# PowerV3.net
KiCad netlist of a schematic drawn in Altium Designer
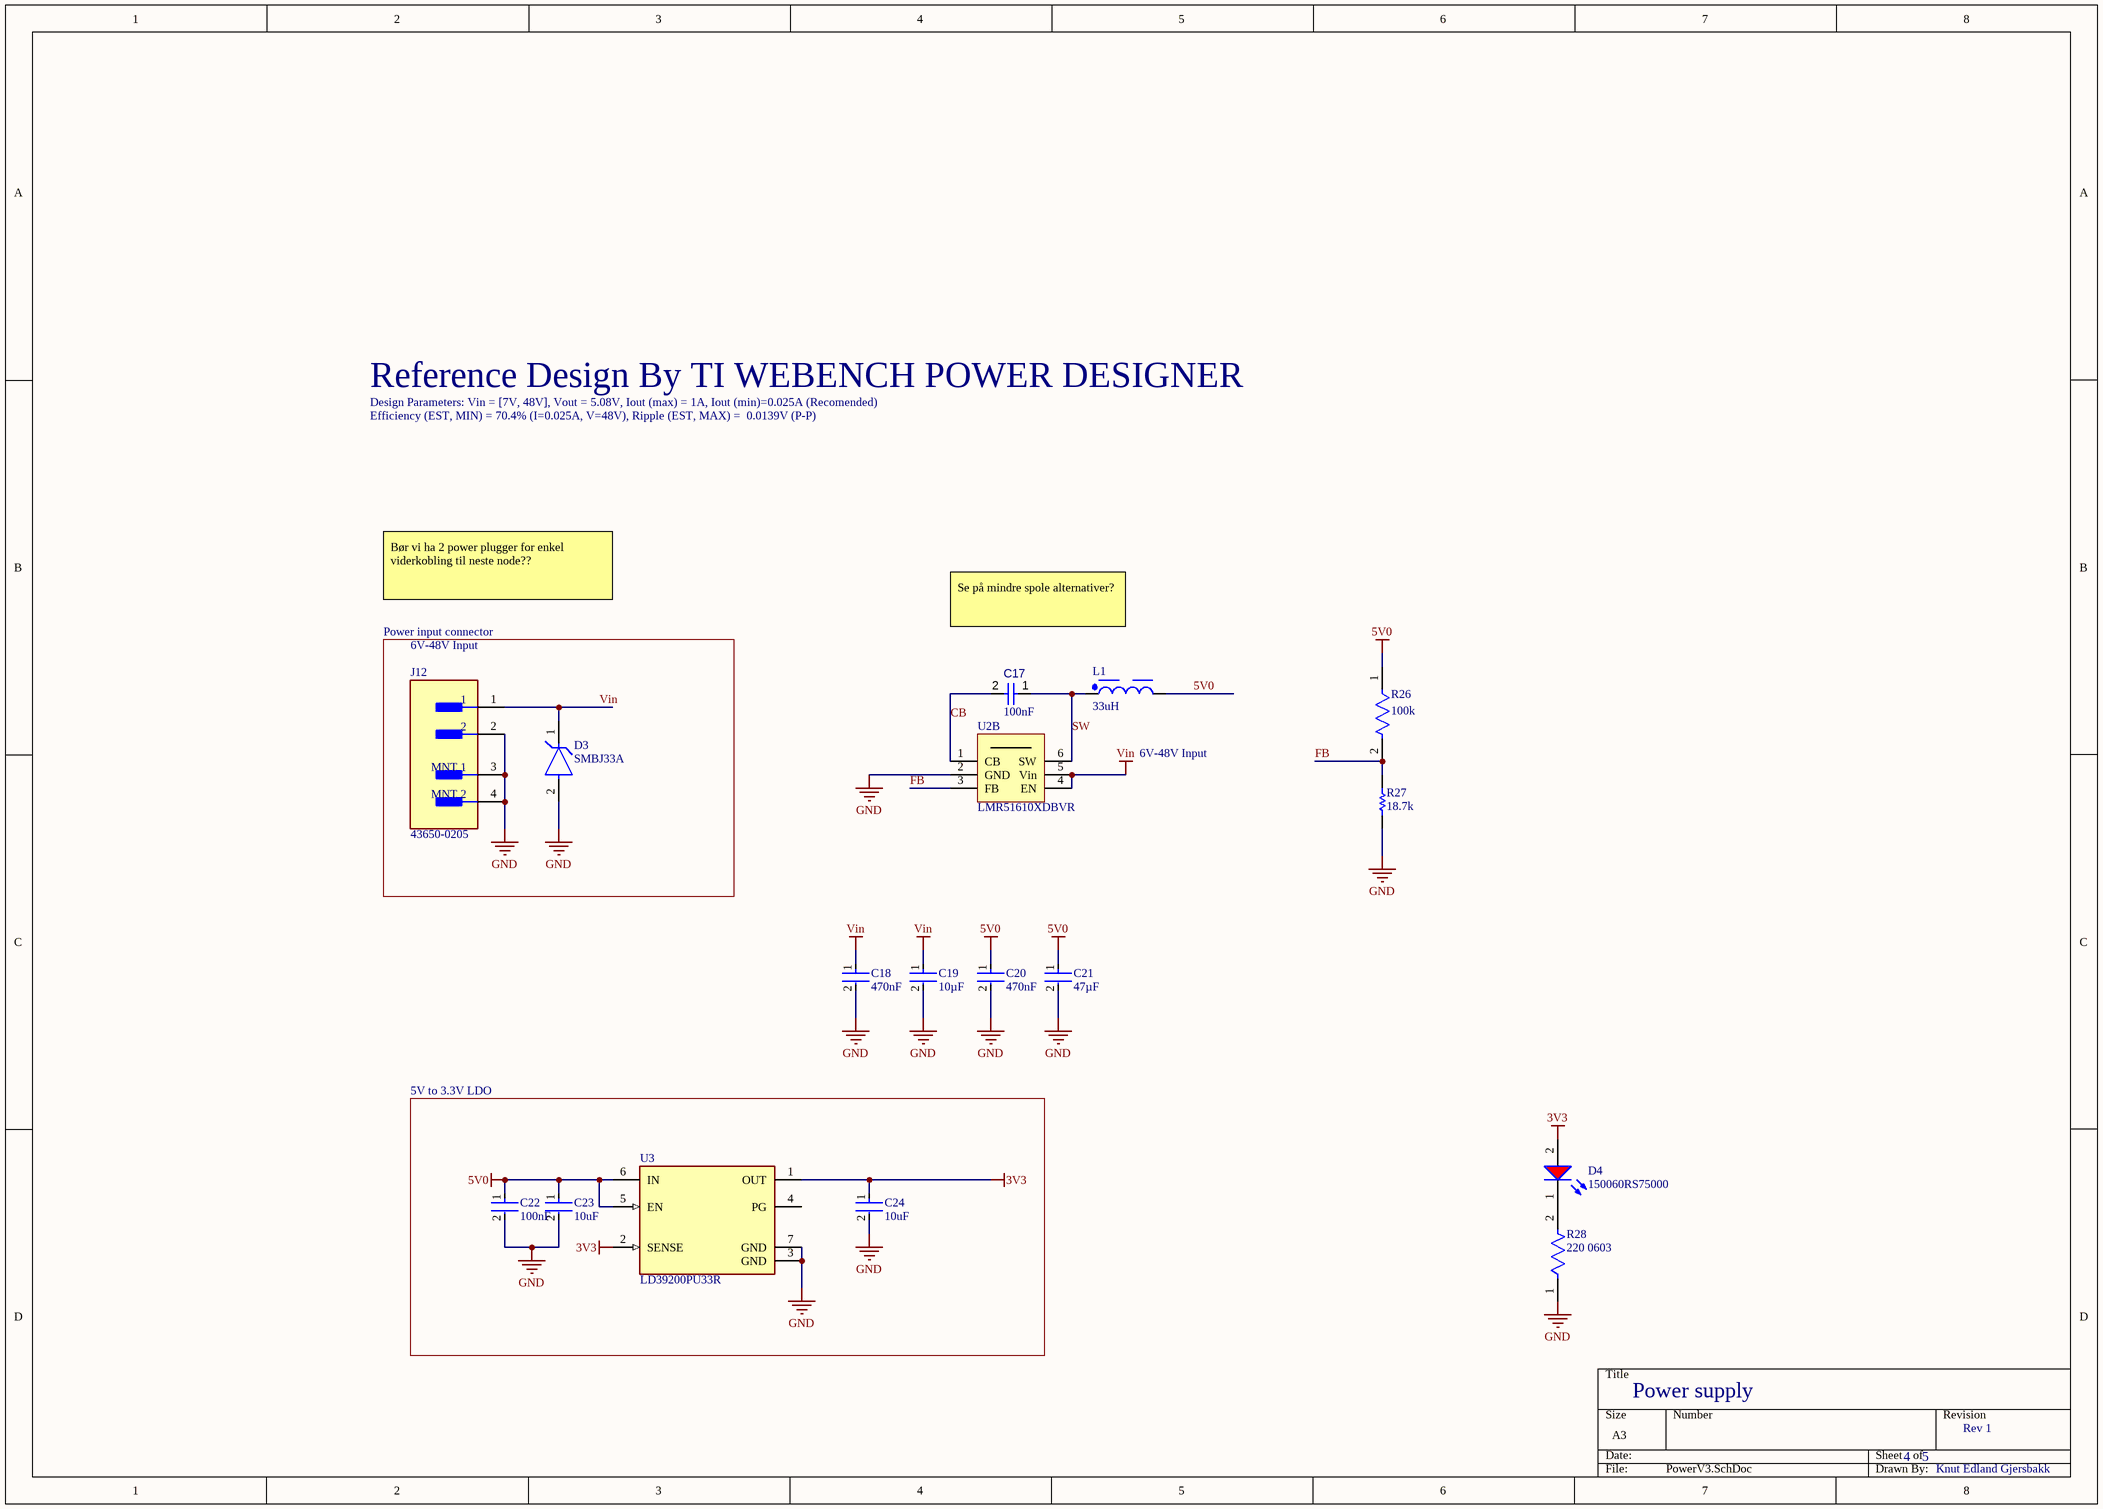
[diagram p0: PowerV3.SchDoc]

(export (version "E")
  (design (tool "Eeschema 10.0.6"))
  (components
    (comp (ref "C17")
      (value "100nF")
      (footprint "CAPC2013X95X50LL10T25")
      (description "Chip Capacitor, 100 nF, +/- 10%, 50 V, 0805 (2012 Metric)")
      (fields (field (name "TOLERANCE") "10%") (field (name "Comment") "Capacitor 100 nF +/-10% 50 V 0805"))
      (libsource (lib "UiS Aerospace") (part "CAP-NP-2"))
    )
    (comp (ref "C18")
      (value "470nF")
      (footprint "FP-CL21-IPC_A")
      (fields (field (name "Comment") "CL21B474KBFNNNF"))
      (libsource (lib "UiS Aerospace") (part "b4654b650e69147ec39a6b967a45e02"))
    )
    (comp (ref "C19")
      (value "10µF")
      (footprint "FP-CL31B106KBHNNNE-IPC_A")
      (fields (field (name "Comment") "CL31B106KBHNNNE"))
      (libsource (lib "UiS Aerospace") (part "b4654b650e69147ec39a6b967a45e02"))
    )
    (comp (ref "C20")
      (value "470nF")
      (footprint "FP-CL21-IPC_A")
      (fields (field (name "Comment") "CL21B474KBFNNNF"))
      (libsource (lib "UiS Aerospace") (part "b4654b650e69147ec39a6b967a45e02"))
    )
    (comp (ref "C21")
      (value "47µF")
      (footprint "FP-GRM31C-0_2-e0_3_0_8-IPC_B")
      (fields (field (name "Comment") "GRM31CR61A476KE15K"))
      (libsource (lib "UiS Aerospace") (part "02cd4be3c70576c341d710602a673aa"))
    )
    (comp (ref "C22")
      (value "100nF")
      (footprint "FP-CL10-IPC_C")
      (description "Cap Ceramic 100nF 16V X7R ±10% Pad SMD 0603 +125°C T/R\r\nCL10B104KO8WPNC")
      (fields (field (name "TOLERANCE") "10%"))
      (libsource (lib "Altium Content Vault") (part "b4654b650e69147ec39a6b967a45e02"))
    )
    (comp (ref "C23")
      (value "10uF")
      (footprint "FP-CL10-IPC_C")
      (description "Cap Ceramic 10uF 16V X6S ±20% Pad SMD 0603 +105°C T/R\r\nCL10X106MO8NRNC")
      (fields (field (name "TOLERANCE") "20%"))
      (libsource (lib "Altium Content Vault") (part "b4654b650e69147ec39a6b967a45e02"))
    )
    (comp (ref "C24")
      (value "10uF")
      (footprint "FP-CL10-IPC_C")
      (description "Cap Ceramic 10uF 16V X6S ±20% Pad SMD 0603 +105°C T/R\r\nCL10X106MO8NRNC")
      (fields (field (name "TOLERANCE") "20%"))
      (libsource (lib "Altium Content Vault") (part "b4654b650e69147ec39a6b967a45e02"))
    )
    (comp (ref "D3")
      (value "SMBJ33A")
      (footprint "FP-SMBJ-MFG")
      (description "TVS DIODE 33V 53.3V DO214AA")
      (fields
        (field (name "MANUFACTURER") "Littelfuse Inc")
        (field (name "OCTOPART") "https://octopart.com/smbj33a-littelfuse-350829")
      )
      (libsource (lib "Altium Content Vault") (part "f813f71cba58e380607f5dd3caf9714"))
    )
    (comp (ref "D4")
      (value "150060RS75000")
      (footprint "WL-SMCW_0603_150060xx75000")
      (description "LED Low-Power Uni-Color Red 630nm 2V 2-Pin Chip 0603(1608Metric) T/R")
      (libsource (lib "Altium Content Vault") (part "LED_Red_2A-1K"))
    )
    (comp (ref "J12")
      (value "43650-0205")
      (footprint "FP-43650-0205-MFG")
      (description "43650-0205 Conn Wire to Board HDR 2 POS 3mm Solder RA Side Entry Thru-Hole Micro-Fit 3.0™ Tray")
      (libsource (lib "Altium Content Vault") (part "56ec3178a87b3978bdc1b3682cd516a"))
    )
    (comp (ref "L1")
      (value "33uH")
      (footprint "WE-PD_1260P")
      (description "General Purpose Inductor")
      (fields (field (name "Comment") "7447706330"))
      (libsource (lib "UiS Aerospace") (part "Inductor - 2"))
    )
    (comp (ref "R26")
      (value "100k")
      (footprint "FP-CRGCQ1206-IPC_A")
      (fields (field (name "Comment") "CRGCQ1206F100K"))
      (libsource (lib "UiS Aerospace") (part "1029c3af85768c4190bb7ad29bc67b5"))
    )
    (comp (ref "R27")
      (value "18.7k")
      (footprint "RESC2013X60X40LL20T25")
      (description "Fixed Resistor, Thin Film, 0.125W, 18700ohm, 100V, 0.1% +/-Tol, 25ppm/Cel, Surface Mount, 0805")
      (fields (field (name "TOLERANCE") "0.1%") (field (name "POWER") "125mW"))
      (libsource (lib "UiS Aerospace") (part "RES"))
    )
    (comp (ref "R28")
      (value "220 0603")
      (footprint "FP-AF0603-IPC_C")
      (description "AF0603JR-07220RL Anti-Sulfurated Chip Resistors Automotive Grade 220Ω 5% 100ppm/°C 0603")
      (fields (field (name "TOLERANCE") "5%"))
      (libsource (lib "Altium Content Vault") (part "1029c3af85768c4190bb7ad29bc67b5"))
    )
    (comp (ref "U2")
      (value "LMR51610XDBVR")
      (footprint "SOT95P280X145-6N")
      (description "SIMPLE SWITCHER® 4.5-V to 65-V, 1-A synchronous buck converter with 25-µA IQ 6-SOT-23 -40 to 150")
      (libsource (lib "UiS Aerospace") (part "LMR51610XDBVR-Symbol-1"))
    )
    (comp (ref "U3")
      (value "LD39200PU33R")
      (footprint "FP-DFN6-7946637-MFG")
      (description "IC REG LINEAR 3.3V 2A 6DFN")
      (libsource (lib "Altium Content Vault") (part "f0cfe00d12cb984572f50007c934a2d"))
    )
  )
  (nets
    (net (code "1") (name "/CB") (class "Default")
      (node (ref "C17") (pin "2") (pinfunction "2_2") (pintype "passive"))
      (node (ref "U2") (pin "1") (pinfunction "CB_1") (pintype "passive"))
    )
    (net (code "2") (name "/FB") (class "Default")
      (node (ref "R26") (pin "2") (pinfunction "2_2") (pintype "passive"))
      (node (ref "R27") (pin "1") (pinfunction "1_1") (pintype "passive"))
      (node (ref "U2") (pin "3") (pinfunction "FB_3") (pintype "passive"))
    )
    (net (code "3") (name "/SW") (class "Default")
      (node (ref "C17") (pin "1") (pinfunction "1_1") (pintype "passive"))
      (node (ref "L1") (pin "1") (pinfunction "1_1") (pintype "passive"))
      (node (ref "U2") (pin "6") (pinfunction "SW_6") (pintype "passive"))
    )
    (net (code "4") (name "3V3") (class "Default")
      (node (ref "C24") (pin "1") (pinfunction "1_1") (pintype "passive"))
      (node (ref "D4") (pin "2") (pinfunction "A_2") (pintype "passive"))
      (node (ref "U3") (pin "1") (pinfunction "OUT_1") (pintype "power_in"))
      (node (ref "U3") (pin "2") (pinfunction "SENSE_2") (pintype "input"))
    )
    (net (code "5") (name "5V0") (class "Default")
      (node (ref "C20") (pin "1") (pinfunction "1_1") (pintype "passive"))
      (node (ref "C21") (pin "1") (pinfunction "1_1") (pintype "passive"))
      (node (ref "C22") (pin "1") (pinfunction "1_1") (pintype "passive"))
      (node (ref "C23") (pin "1") (pinfunction "1_1") (pintype "passive"))
      (node (ref "L1") (pin "2") (pinfunction "2_2") (pintype "passive"))
      (node (ref "R26") (pin "1") (pinfunction "1_1") (pintype "passive"))
      (node (ref "U3") (pin "5") (pinfunction "EN_5") (pintype "input"))
      (node (ref "U3") (pin "6") (pinfunction "IN_6") (pintype "power_in"))
    )
    (net (code "6") (name "GND") (class "Default")
      (node (ref "C18") (pin "2") (pinfunction "2_2") (pintype "passive"))
      (node (ref "C19") (pin "2") (pinfunction "2_2") (pintype "passive"))
      (node (ref "C20") (pin "2") (pinfunction "2_2") (pintype "passive"))
      (node (ref "C21") (pin "2") (pinfunction "2_2") (pintype "passive"))
      (node (ref "C22") (pin "2") (pinfunction "2_2") (pintype "passive"))
      (node (ref "C23") (pin "2") (pinfunction "2_2") (pintype "passive"))
      (node (ref "C24") (pin "2") (pinfunction "2_2") (pintype "passive"))
      (node (ref "D3") (pin "2") (pinfunction "A_2") (pintype "passive"))
      (node (ref "J12") (pin "2") (pinfunction "2_2") (pintype "passive"))
      (node (ref "J12") (pin "3") (pinfunction "MNT_1_3") (pintype "passive"))
      (node (ref "J12") (pin "4") (pinfunction "MNT_2_4") (pintype "passive"))
      (node (ref "R27") (pin "2") (pinfunction "2_2") (pintype "passive"))
      (node (ref "R28") (pin "1") (pinfunction "1_1") (pintype "passive"))
      (node (ref "U2") (pin "2") (pinfunction "GND_2") (pintype "passive"))
      (node (ref "U3") (pin "3") (pinfunction "GND_3") (pintype "power_in"))
      (node (ref "U3") (pin "7") (pinfunction "GND_7") (pintype "power_in"))
    )
    (net (code "7") (name "Net-(D4-K)") (class "Default")
      (node (ref "D4") (pin "1") (pinfunction "K_1") (pintype "passive"))
      (node (ref "R28") (pin "2") (pinfunction "2_2") (pintype "passive"))
    )
    (net (code "8") (name "Vin") (class "Default")
      (node (ref "C18") (pin "1") (pinfunction "1_1") (pintype "passive"))
      (node (ref "C19") (pin "1") (pinfunction "1_1") (pintype "passive"))
      (node (ref "D3") (pin "1") (pinfunction "C_1") (pintype "passive"))
      (node (ref "J12") (pin "1") (pinfunction "1_1") (pintype "passive"))
      (node (ref "U2") (pin "4") (pinfunction "EN_4") (pintype "passive"))
      (node (ref "U2") (pin "5") (pinfunction "Vin_5") (pintype "passive"))
    )
    (net (code "9") (name "unconnected-(U3-PG-Pad4)") (class "Default")
      (node (ref "U3") (pin "4") (pinfunction "PG_4") (pintype "open_collector"))
    )
  )
)
